# Power.net
KiCad netlist of a schematic drawn in Altium Designer
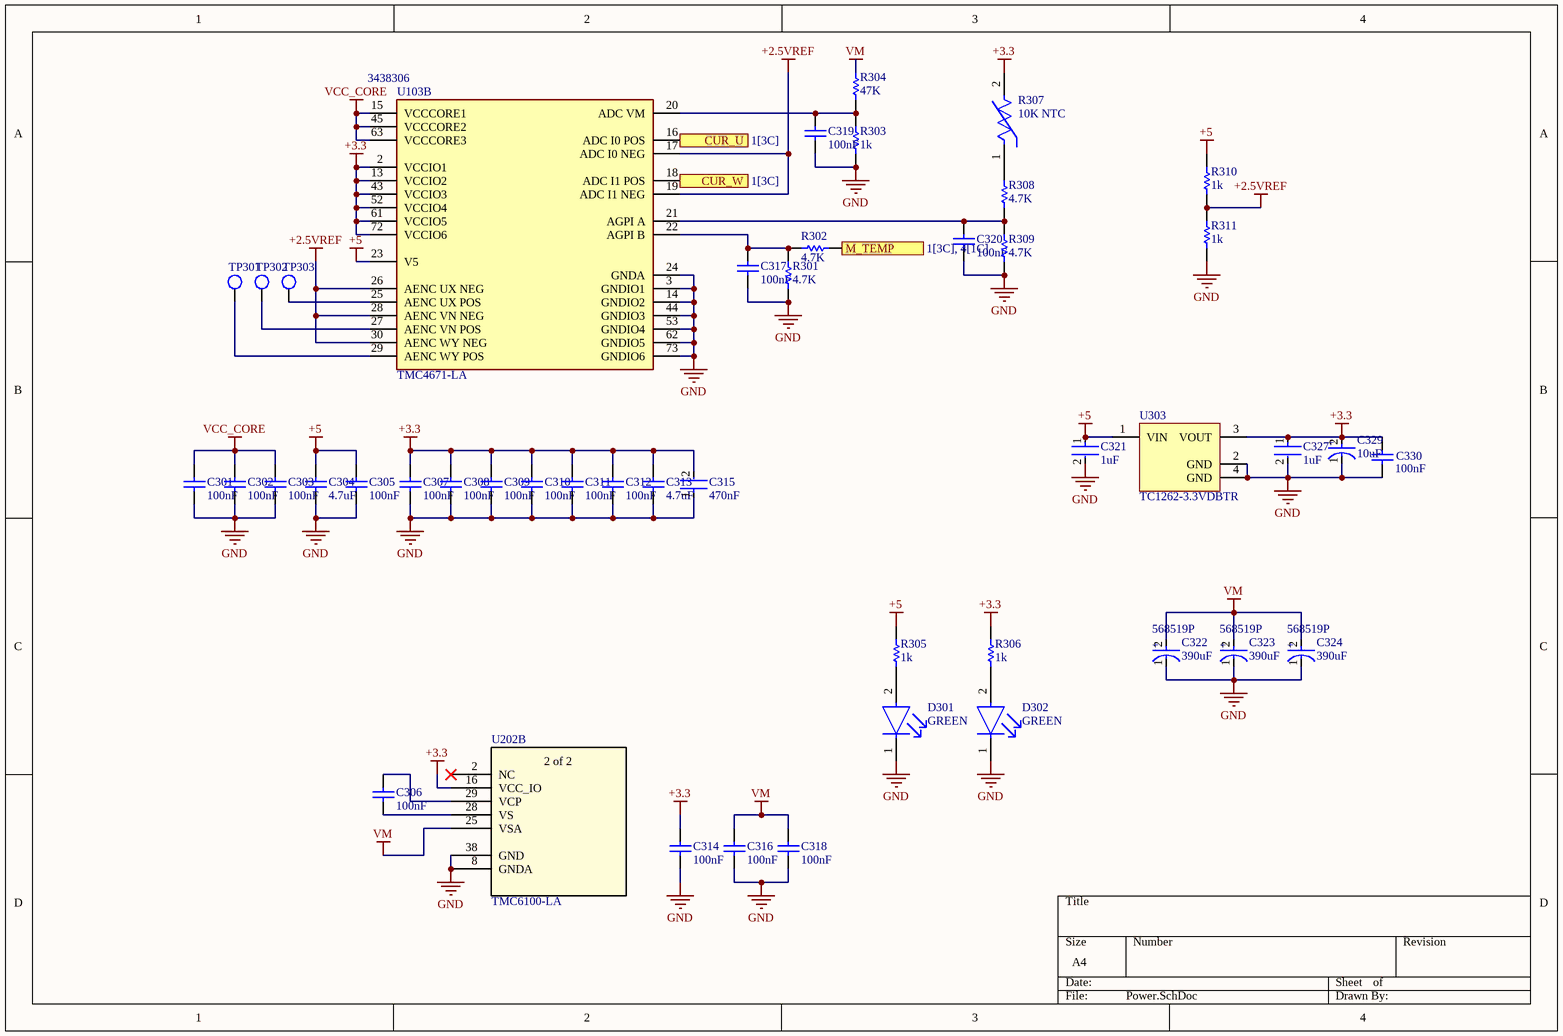
[diagram p0: Power.SchDoc]

(export (version "E")
  (design (tool "Eeschema 10.0.6"))
  (components
    (comp (ref "C301")
      (value "100nF")
      (footprint "CAPC1608X90X35NL10T15")
      (description "Chip Capacitor, 0.1 uF, +/- 10%, 50 V, -55 to 125 degC, 0603 (1608 Metric), RoHS, Tape and Reel")
      (fields (field (name "TOLERANCE") "10%") (field (name "VOLTAGE") "50V"))
      (libsource (lib "Altium Content Vault") (part "CAP-NP-2"))
    )
    (comp (ref "C302")
      (value "100nF")
      (footprint "CAPC1608X90X35NL10T15")
      (description "Chip Capacitor, 0.1 uF, +/- 10%, 50 V, -55 to 125 degC, 0603 (1608 Metric), RoHS, Tape and Reel")
      (fields (field (name "TOLERANCE") "10%") (field (name "VOLTAGE") "50V"))
      (libsource (lib "Altium Content Vault") (part "CAP-NP-2"))
    )
    (comp (ref "C303")
      (value "100nF")
      (footprint "CAPC1608X90X35NL10T15")
      (description "Chip Capacitor, 0.1 uF, +/- 10%, 50 V, -55 to 125 degC, 0603 (1608 Metric), RoHS, Tape and Reel")
      (fields (field (name "TOLERANCE") "10%") (field (name "VOLTAGE") "50V"))
      (libsource (lib "Altium Content Vault") (part "CAP-NP-2"))
    )
    (comp (ref "C304")
      (value "4.7uF")
      (footprint "CAPC2013X145X50ML20T25")
      (fields (field (name "PART NUMBER") "C0805C475K4RACTU") (field (name "MANUFACTURER") "Kemet"))
      (libsource (lib "Altium Content Vault") (part "CAP"))
    )
    (comp (ref "C305")
      (value "100nF")
      (footprint "CAPC1608X90X35NL10T15")
      (description "Chip Capacitor, 0.1 uF, +/- 10%, 50 V, -55 to 125 degC, 0603 (1608 Metric), RoHS, Tape and Reel")
      (fields (field (name "TOLERANCE") "10%") (field (name "VOLTAGE") "50V"))
      (libsource (lib "Altium Content Vault") (part "CAP-NP-2"))
    )
    (comp (ref "C306")
      (value "100nF")
      (footprint "CAPC2013X145X20ML20")
      (description "Chip Capacitor, 100 nF, +/- 10%, 100 V, -55 to 1255 degC, 0805 (2012 Metric), RoHS, Tape and Reel")
      (fields (field (name "MANUFACTURER") "TDK") (field (name "TOLERANCE") "±10%"))
      (libsource (lib "Altium Content Vault") (part "CAP-NP-2"))
    )
    (comp (ref "C307")
      (value "100nF")
      (footprint "CAPC1608X90X35NL10T15")
      (description "Chip Capacitor, 0.1 uF, +/- 10%, 50 V, -55 to 125 degC, 0603 (1608 Metric), RoHS, Tape and Reel")
      (fields (field (name "TOLERANCE") "10%") (field (name "VOLTAGE") "50V"))
      (libsource (lib "Altium Content Vault") (part "CAP-NP-2"))
    )
    (comp (ref "C308")
      (value "100nF")
      (footprint "CAPC1608X90X35NL10T15")
      (description "Chip Capacitor, 0.1 uF, +/- 10%, 50 V, -55 to 125 degC, 0603 (1608 Metric), RoHS, Tape and Reel")
      (fields (field (name "TOLERANCE") "10%") (field (name "VOLTAGE") "50V"))
      (libsource (lib "Altium Content Vault") (part "CAP-NP-2"))
    )
    (comp (ref "C309")
      (value "100nF")
      (footprint "CAPC1608X90X35NL10T15")
      (description "Chip Capacitor, 0.1 uF, +/- 10%, 50 V, -55 to 125 degC, 0603 (1608 Metric), RoHS, Tape and Reel")
      (fields (field (name "TOLERANCE") "10%") (field (name "VOLTAGE") "50V"))
      (libsource (lib "Altium Content Vault") (part "CAP-NP-2"))
    )
    (comp (ref "C310")
      (value "100nF")
      (footprint "CAPC1608X90X35NL10T15")
      (description "Chip Capacitor, 0.1 uF, +/- 10%, 50 V, -55 to 125 degC, 0603 (1608 Metric), RoHS, Tape and Reel")
      (fields (field (name "TOLERANCE") "10%") (field (name "VOLTAGE") "50V"))
      (libsource (lib "Altium Content Vault") (part "CAP-NP-2"))
    )
    (comp (ref "C311")
      (value "100nF")
      (footprint "CAPC1608X90X35NL10T15")
      (description "Chip Capacitor, 0.1 uF, +/- 10%, 50 V, -55 to 125 degC, 0603 (1608 Metric), RoHS, Tape and Reel")
      (fields (field (name "TOLERANCE") "10%") (field (name "VOLTAGE") "50V"))
      (libsource (lib "Altium Content Vault") (part "CAP-NP-2"))
    )
    (comp (ref "C312")
      (value "100nF")
      (footprint "CAPC1608X90X35NL10T15")
      (description "Chip Capacitor, 0.1 uF, +/- 10%, 50 V, -55 to 125 degC, 0603 (1608 Metric), RoHS, Tape and Reel")
      (fields (field (name "TOLERANCE") "10%") (field (name "VOLTAGE") "50V"))
      (libsource (lib "Altium Content Vault") (part "CAP-NP-2"))
    )
    (comp (ref "C313")
      (value "4.7uF")
      (footprint "CAPC2013X145X50ML20T25")
      (fields (field (name "PART NUMBER") "C0805C475K4RACTU") (field (name "MANUFACTURER") "Kemet"))
      (libsource (lib "Altium Content Vault") (part "CAP"))
    )
    (comp (ref "C314")
      (value "100nF")
      (footprint "CAPC1608X90X35NL10T15")
      (description "Chip Capacitor, 0.1 uF, +/- 10%, 50 V, -55 to 125 degC, 0603 (1608 Metric), RoHS, Tape and Reel")
      (fields (field (name "TOLERANCE") "10%") (field (name "VOLTAGE") "50V"))
      (libsource (lib "Altium Content Vault") (part "CAP-NP-2"))
    )
    (comp (ref "C315")
      (value "470nF")
      (footprint "FP-0603-L_1_6_0_1-W_0_8_0-IPC_B")
      (description "None")
      (fields (field (name "TOLERANCE") "10%") (field (name "VOLTAGE") "50V"))
      (libsource (lib "Altium Content Vault") (part "02cd4be3c70576c341d710602a673aa"))
    )
    (comp (ref "C316")
      (value "100nF")
      (footprint "CAPC2013X145X20ML20")
      (description "Chip Capacitor, 100 nF, +/- 10%, 100 V, -55 to 1255 degC, 0805 (2012 Metric), RoHS, Tape and Reel")
      (fields (field (name "MANUFACTURER") "TDK") (field (name "TOLERANCE") "±10%"))
      (libsource (lib "Altium Content Vault") (part "CAP-NP-2"))
    )
    (comp (ref "C317")
      (value "100nF")
      (footprint "CAPC1608X90X35NL10T15")
      (description "Chip Capacitor, 0.1 uF, +/- 10%, 50 V, -55 to 125 degC, 0603 (1608 Metric), RoHS, Tape and Reel")
      (fields (field (name "TOLERANCE") "10%") (field (name "VOLTAGE") "50V"))
      (libsource (lib "Altium Content Vault") (part "CAP-NP-2"))
    )
    (comp (ref "C318")
      (value "100nF")
      (footprint "CAPC2013X145X20ML20")
      (description "Chip Capacitor, 100 nF, +/- 10%, 100 V, -55 to 1255 degC, 0805 (2012 Metric), RoHS, Tape and Reel")
      (fields (field (name "MANUFACTURER") "TDK") (field (name "TOLERANCE") "±10%"))
      (libsource (lib "Altium Content Vault") (part "CAP-NP-2"))
    )
    (comp (ref "C319")
      (value "100nF")
      (footprint "CAPC1608X90X35NL10T15")
      (description "Chip Capacitor, 0.1 uF, +/- 10%, 50 V, -55 to 125 degC, 0603 (1608 Metric), RoHS, Tape and Reel")
      (fields (field (name "TOLERANCE") "10%") (field (name "VOLTAGE") "50V"))
      (libsource (lib "Altium Content Vault") (part "CAP-NP-2"))
    )
    (comp (ref "C320")
      (value "100nF")
      (footprint "CAPC1608X90X35NL10T15")
      (description "Chip Capacitor, 0.1 uF, +/- 10%, 50 V, -55 to 125 degC, 0603 (1608 Metric), RoHS, Tape and Reel")
      (fields (field (name "TOLERANCE") "10%") (field (name "VOLTAGE") "50V"))
      (libsource (lib "Altium Content Vault") (part "CAP-NP-2"))
    )
    (comp (ref "C321")
      (value "1uF")
      (footprint "FP-CL10-IPC_B")
      (description "Cap Ceramic 1uF 25V X5R ±10% Pad SMD 0603 +85°C T/R")
      (fields (field (name "VOLTAGE") "25V") (field (name "TOLERANCE") "10%"))
      (libsource (lib "Altium Content Vault") (part "b4654b650e69147ec39a6b967a45e02"))
    )
    (comp (ref "C322")
      (value "390uF")
      (footprint "FP-FC-G-MFG")
      (description "Cap Aluminum 390uF 35V 20% (10 X 10.2mm) SMD 0.08 Ohm 850mA 2000 hr 105°C Embossed T/R")
      (fields
        (field (name "TOLERANCE") "20%")
        (field (name "VOLTAGE") "35V")
        (field (name "SUPPLIER PART NUMBER 1") "568519P")
      )
      (libsource (lib "Altium Content Vault") (part "8eef7423fb450d55d321f8a63fae760"))
    )
    (comp (ref "C323")
      (value "390uF")
      (footprint "FP-FC-G-MFG")
      (description "Cap Aluminum 390uF 35V 20% (10 X 10.2mm) SMD 0.08 Ohm 850mA 2000 hr 105°C Embossed T/R")
      (fields
        (field (name "TOLERANCE") "20%")
        (field (name "VOLTAGE") "35V")
        (field (name "SUPPLIER PART NUMBER 1") "568519P")
      )
      (libsource (lib "Altium Content Vault") (part "8eef7423fb450d55d321f8a63fae760"))
    )
    (comp (ref "C324")
      (value "390uF")
      (footprint "FP-FC-G-MFG")
      (description "Cap Aluminum 390uF 35V 20% (10 X 10.2mm) SMD 0.08 Ohm 850mA 2000 hr 105°C Embossed T/R")
      (fields
        (field (name "TOLERANCE") "20%")
        (field (name "VOLTAGE") "35V")
        (field (name "SUPPLIER PART NUMBER 1") "568519P")
      )
      (libsource (lib "Altium Content Vault") (part "8eef7423fb450d55d321f8a63fae760"))
    )
    (comp (ref "C327")
      (value "1uF")
      (footprint "FP-CL10-IPC_B")
      (description "Cap Ceramic 1uF 25V X5R ±10% Pad SMD 0603 +85°C T/R")
      (fields (field (name "VOLTAGE") "25V") (field (name "TOLERANCE") "10%"))
      (libsource (lib "Altium Content Vault") (part "b4654b650e69147ec39a6b967a45e02"))
    )
    (comp (ref "C329")
      (value "10uF")
      (footprint "FP-TAJA-MFG")
      (description "10uF 10V  ±10% 3Ω 1206  SMD Tantalum Capacitor")
      (fields (field (name "TOLERANCE") "10%") (field (name "VOLTAGE") "10V"))
      (libsource (lib "Altium Content Vault") (part "203bc49f2ac43e59fd269a8c329ed05"))
    )
    (comp (ref "C330")
      (value "100nF")
      (footprint "CAPC1608X90X35NL10T15")
      (description "Chip Capacitor, 0.1 uF, +/- 10%, 50 V, -55 to 125 degC, 0603 (1608 Metric), RoHS, Tape and Reel")
      (fields (field (name "TOLERANCE") "10%") (field (name "VOLTAGE") "50V"))
      (libsource (lib "Altium Content Vault") (part "CAP-NP-2"))
    )
    (comp (ref "D301")
      (value "GREEN")
      (footprint "FP-LTST-C190GKT-MFG")
      (description "LED GREEN CLEAR CHIP SMD")
      (fields (field (name "VOLTAGE") "2V"))
      (libsource (lib "Altium Content Vault") (part "8706943c75ba83719d021d2fdc84c58"))
    )
    (comp (ref "D302")
      (value "GREEN")
      (footprint "FP-LTST-C190GKT-MFG")
      (description "LED GREEN CLEAR CHIP SMD")
      (fields (field (name "VOLTAGE") "2V"))
      (libsource (lib "Altium Content Vault") (part "8706943c75ba83719d021d2fdc84c58"))
    )
    (comp (ref "R301")
      (value "4.7K")
      (footprint "RESC1608X55X30NL15T15")
      (fields (field (name "TOLERANCE") "5%"))
      (libsource (lib "Altium Content Vault") (part "RES-2"))
    )
    (comp (ref "R302")
      (value "4.7K")
      (footprint "RESC1608X55X30NL15T15")
      (fields (field (name "TOLERANCE") "5%"))
      (libsource (lib "Altium Content Vault") (part "RES-2"))
    )
    (comp (ref "R303")
      (value "1k")
      (footprint "RESC1608X55X30ML15T15")
      (fields (field (name "PART NUMBER") "ERJ-3EKF1001V") (field (name "MANUFACTURER") "Panasonic"))
      (libsource (lib "Altium Content Vault") (part "RES"))
    )
    (comp (ref "R304")
      (value "47K")
      (footprint "RESC1608X55X30NL15T15")
      (description "Chip Resistor, 47 KOhm, +/- 1%, 0.1 W, -55 to 155 degC, 0603 (1608 Metric), RoHS, Tape and Reel")
      (libsource (lib "Altium Content Vault") (part "RES-2"))
    )
    (comp (ref "R305")
      (value "1k")
      (footprint "RESC1608X55X30ML15T15")
      (fields (field (name "PART NUMBER") "ERJ-3EKF1001V") (field (name "MANUFACTURER") "Panasonic"))
      (libsource (lib "Altium Content Vault") (part "RES"))
    )
    (comp (ref "R306")
      (value "1k")
      (footprint "RESC1608X55X30ML15T15")
      (fields (field (name "PART NUMBER") "ERJ-3EKF1001V") (field (name "MANUFACTURER") "Panasonic"))
      (libsource (lib "Altium Content Vault") (part "RES"))
    )
    (comp (ref "R307")
      (value "10K NTC")
      (footprint "FP-NCP18-0_15-IPC_A")
      (description "NTC Thermistor for Temperature Sensor, 0603, 10kΩ, 1%, 0.1mA, 5V")
      (fields (field (name "TOLERANCE") "1%"))
      (libsource (lib "Altium Content Vault") (part "3b148a6ebabc5fb4d708a66c052d352"))
    )
    (comp (ref "R308")
      (value "4.7K")
      (footprint "RESC1608X55X30NL15T15")
      (fields (field (name "TOLERANCE") "5%"))
      (libsource (lib "Altium Content Vault") (part "RES-2"))
    )
    (comp (ref "R309")
      (value "4.7K")
      (footprint "RESC1608X55X30NL15T15")
      (fields (field (name "TOLERANCE") "5%"))
      (libsource (lib "Altium Content Vault") (part "RES-2"))
    )
    (comp (ref "R310")
      (value "1k")
      (footprint "RESC1608X55X30ML15T15")
      (fields (field (name "PART NUMBER") "ERJ-3EKF1001V") (field (name "MANUFACTURER") "Panasonic"))
      (libsource (lib "Altium Content Vault") (part "RES"))
    )
    (comp (ref "R311")
      (value "1k")
      (footprint "RESC1608X55X30ML15T15")
      (fields (field (name "PART NUMBER") "ERJ-3EKF1001V") (field (name "MANUFACTURER") "Panasonic"))
      (libsource (lib "Altium Content Vault") (part "RES"))
    )
    (comp (ref "TP301")
      (value "TestPoint")
      (footprint "PCBComponent_1")
      (libsource (lib "Testpoint") (part "TestPoint"))
    )
    (comp (ref "TP302")
      (value "TestPoint")
      (footprint "PCBComponent_1")
      (libsource (lib "Testpoint") (part "TestPoint"))
    )
    (comp (ref "TP303")
      (value "TestPoint")
      (footprint "PCBComponent_1")
      (libsource (lib "Testpoint") (part "TestPoint"))
    )
    (comp (ref "U103")
      (value "TMC4671-LA")
      (footprint "FP-TMC4671-LA-IPC_A")
      (description "SERVO CONTROLLER IC, QFN76")
      (fields (field (name "SUPPLIER PART NUMBER 1") "3438306"))
      (libsource (lib "Altium Content Vault") (part "fddf9d8c5dbc63ee6fb3cd60f877672"))
    )
    (comp (ref "U202")
      (value "TMC6100-LA")
      (footprint "QFN37_7X7_TRI-M")
      (description "No Description Available")
      (libsource (lib "TMC6100-LA") (part "TMC6100-LA"))
    )
    (comp (ref "U303")
      (value "TC1262-3.3VDBTR")
      (footprint "SOT-223-DB3_N")
      (description "500mA Fixed Output CMOS LDO, 3-Pin SOT-223, Extended Temperature, Tape and Reel")
      (libsource (lib "Altium Content Vault") (part "PM-LINEREG-TC1262-IL4"))
    )
  )
  (nets
    (net (code "1") (name "+2.5VREF") (class "Default")
      (node (ref "R310") (pin "1") (pinfunction "1_1") (pintype "passive"))
      (node (ref "R311") (pin "2") (pinfunction "2_2") (pintype "passive"))
      (node (ref "U103") (pin "17") (pinfunction "ADC_I0_NEG_17") (pintype "passive"))
      (node (ref "U103") (pin "19") (pinfunction "ADC_I1_NEG_19") (pintype "passive"))
      (node (ref "U103") (pin "26") (pinfunction "AENC_UX_NEG_26") (pintype "passive"))
      (node (ref "U103") (pin "28") (pinfunction "AENC_VN_NEG_28") (pintype "passive"))
      (node (ref "U103") (pin "30") (pinfunction "AENC_WY_NEG_30") (pintype "passive"))
    )
    (net (code "2") (name "+3.3") (class "Default")
      (node (ref "C307") (pin "2") (pinfunction "2_2") (pintype "passive"))
      (node (ref "C308") (pin "2") (pinfunction "2_2") (pintype "passive"))
      (node (ref "C309") (pin "2") (pinfunction "2_2") (pintype "passive"))
      (node (ref "C310") (pin "2") (pinfunction "2_2") (pintype "passive"))
      (node (ref "C311") (pin "2") (pinfunction "2_2") (pintype "passive"))
      (node (ref "C312") (pin "2") (pinfunction "2_2") (pintype "passive"))
      (node (ref "C313") (pin "2") (pinfunction "2_2") (pintype "passive"))
      (node (ref "C314") (pin "2") (pinfunction "2_2") (pintype "passive"))
      (node (ref "C315") (pin "2") (pinfunction "2_2") (pintype "passive"))
      (node (ref "C327") (pin "1") (pinfunction "1_1") (pintype "passive"))
      (node (ref "C329") (pin "2") (pinfunction "A_2") (pintype "passive"))
      (node (ref "C330") (pin "2") (pinfunction "2_2") (pintype "passive"))
      (node (ref "R306") (pin "2") (pinfunction "2_2") (pintype "passive"))
      (node (ref "R307") (pin "2") (pinfunction "2_2") (pintype "passive"))
      (node (ref "U103") (pin "13") (pinfunction "VCCIO2_13") (pintype "power_in"))
      (node (ref "U103") (pin "2") (pinfunction "VCCIO1_2") (pintype "power_in"))
      (node (ref "U103") (pin "43") (pinfunction "VCCIO3_43") (pintype "power_in"))
      (node (ref "U103") (pin "52") (pinfunction "VCCIO4_52") (pintype "power_in"))
      (node (ref "U103") (pin "61") (pinfunction "VCCIO5_61") (pintype "power_in"))
      (node (ref "U103") (pin "72") (pinfunction "VCCIO6_72") (pintype "power_in"))
      (node (ref "U202") (pin "16") (pinfunction "VCC_IO_16") (pintype "power_in"))
      (node (ref "U303") (pin "3") (pinfunction "VOUT_3") (pintype "power_in"))
    )
    (net (code "3") (name "+5") (class "Default")
      (node (ref "C304") (pin "2") (pinfunction "2_2") (pintype "passive"))
      (node (ref "C305") (pin "2") (pinfunction "2_2") (pintype "passive"))
      (node (ref "C321") (pin "1") (pinfunction "1_1") (pintype "passive"))
      (node (ref "R305") (pin "2") (pinfunction "2_2") (pintype "passive"))
      (node (ref "R310") (pin "2") (pinfunction "2_2") (pintype "passive"))
      (node (ref "U103") (pin "23") (pinfunction "V5_23") (pintype "power_in"))
      (node (ref "U303") (pin "1") (pinfunction "VIN_1") (pintype "power_in"))
    )
    (net (code "4") (name "/CUR_U") (class "Default")
      (node (ref "U103") (pin "16") (pinfunction "ADC_I0_POS_16") (pintype "passive"))
    )
    (net (code "5") (name "/CUR_W") (class "Default")
      (node (ref "U103") (pin "18") (pinfunction "ADC_I1_POS_18") (pintype "passive"))
    )
    (net (code "6") (name "/M_TEMP") (class "Default")
      (node (ref "R302") (pin "2") (pinfunction "2_2") (pintype "passive"))
    )
    (net (code "7") (name "GND") (class "Default")
      (node (ref "C301") (pin "1") (pinfunction "1_1") (pintype "passive"))
      (node (ref "C302") (pin "1") (pinfunction "1_1") (pintype "passive"))
      (node (ref "C303") (pin "1") (pinfunction "1_1") (pintype "passive"))
      (node (ref "C304") (pin "1") (pinfunction "1_1") (pintype "passive"))
      (node (ref "C305") (pin "1") (pinfunction "1_1") (pintype "passive"))
      (node (ref "C307") (pin "1") (pinfunction "1_1") (pintype "passive"))
      (node (ref "C308") (pin "1") (pinfunction "1_1") (pintype "passive"))
      (node (ref "C309") (pin "1") (pinfunction "1_1") (pintype "passive"))
      (node (ref "C310") (pin "1") (pinfunction "1_1") (pintype "passive"))
      (node (ref "C311") (pin "1") (pinfunction "1_1") (pintype "passive"))
      (node (ref "C312") (pin "1") (pinfunction "1_1") (pintype "passive"))
      (node (ref "C313") (pin "1") (pinfunction "1_1") (pintype "passive"))
      (node (ref "C314") (pin "1") (pinfunction "1_1") (pintype "passive"))
      (node (ref "C315") (pin "1") (pinfunction "1_1") (pintype "passive"))
      (node (ref "C316") (pin "2") (pinfunction "2_2") (pintype "passive"))
      (node (ref "C317") (pin "1") (pinfunction "1_1") (pintype "passive"))
      (node (ref "C318") (pin "2") (pinfunction "2_2") (pintype "passive"))
      (node (ref "C319") (pin "1") (pinfunction "1_1") (pintype "passive"))
      (node (ref "C320") (pin "1") (pinfunction "1_1") (pintype "passive"))
      (node (ref "C321") (pin "2") (pinfunction "2_2") (pintype "passive"))
      (node (ref "C322") (pin "1") (pinfunction "C_1") (pintype "passive"))
      (node (ref "C323") (pin "1") (pinfunction "C_1") (pintype "passive"))
      (node (ref "C324") (pin "1") (pinfunction "C_1") (pintype "passive"))
      (node (ref "C327") (pin "2") (pinfunction "2_2") (pintype "passive"))
      (node (ref "C329") (pin "1") (pinfunction "C_1") (pintype "passive"))
      (node (ref "C330") (pin "1") (pinfunction "1_1") (pintype "passive"))
      (node (ref "D301") (pin "1") (pinfunction "C_1") (pintype "passive"))
      (node (ref "D302") (pin "1") (pinfunction "C_1") (pintype "passive"))
      (node (ref "R301") (pin "1") (pinfunction "1_1") (pintype "passive"))
      (node (ref "R303") (pin "1") (pinfunction "1_1") (pintype "passive"))
      (node (ref "R309") (pin "1") (pinfunction "1_1") (pintype "passive"))
      (node (ref "R311") (pin "1") (pinfunction "1_1") (pintype "passive"))
      (node (ref "U103") (pin "14") (pinfunction "GNDIO2_14") (pintype "power_in"))
      (node (ref "U103") (pin "24") (pinfunction "GNDA_24") (pintype "power_in"))
      (node (ref "U103") (pin "3") (pinfunction "GNDIO1_3") (pintype "power_in"))
      (node (ref "U103") (pin "44") (pinfunction "GNDIO3_44") (pintype "power_in"))
      (node (ref "U103") (pin "53") (pinfunction "GNDIO4_53") (pintype "power_in"))
      (node (ref "U103") (pin "62") (pinfunction "GNDIO5_62") (pintype "power_in"))
      (node (ref "U103") (pin "73") (pinfunction "GNDIO6_73") (pintype "power_in"))
      (node (ref "U202") (pin "38") (pinfunction "GND_38") (pintype "power_in"))
      (node (ref "U202") (pin "8") (pinfunction "GNDA_8") (pintype "power_in"))
      (node (ref "U303") (pin "2") (pinfunction "GND_2") (pintype "power_in"))
      (node (ref "U303") (pin "4") (pinfunction "GND_4") (pintype "power_in"))
    )
    (net (code "8") (name "Net-(D301-A)") (class "Default")
      (node (ref "D301") (pin "2") (pinfunction "A_2") (pintype "passive"))
      (node (ref "R305") (pin "1") (pinfunction "1_1") (pintype "passive"))
    )
    (net (code "9") (name "Net-(D302-A)") (class "Default")
      (node (ref "D302") (pin "2") (pinfunction "A_2") (pintype "passive"))
      (node (ref "R306") (pin "1") (pinfunction "1_1") (pintype "passive"))
    )
    (net (code "10") (name "Net-(R307-Pad1)") (class "Default")
      (node (ref "R307") (pin "1") (pinfunction "1_1") (pintype "passive"))
      (node (ref "R308") (pin "2") (pinfunction "2_2") (pintype "passive"))
    )
    (net (code "11") (name "Net-(U103B-ADC_VM)") (class "Default")
      (node (ref "C319") (pin "2") (pinfunction "2_2") (pintype "passive"))
      (node (ref "R303") (pin "2") (pinfunction "2_2") (pintype "passive"))
      (node (ref "R304") (pin "1") (pinfunction "1_1") (pintype "passive"))
      (node (ref "U103") (pin "20") (pinfunction "ADC_VM_20") (pintype "passive"))
    )
    (net (code "12") (name "Net-(U103B-AENC_UX_POS)") (class "Default")
      (node (ref "TP303") (pin "1") (pinfunction "1_1") (pintype "passive"))
      (node (ref "U103") (pin "25") (pinfunction "AENC_UX_POS_25") (pintype "passive"))
    )
    (net (code "13") (name "Net-(U103B-AENC_VN_POS)") (class "Default")
      (node (ref "TP302") (pin "1") (pinfunction "1_1") (pintype "passive"))
      (node (ref "U103") (pin "27") (pinfunction "AENC_VN_POS_27") (pintype "passive"))
    )
    (net (code "14") (name "Net-(U103B-AENC_WY_POS)") (class "Default")
      (node (ref "TP301") (pin "1") (pinfunction "1_1") (pintype "passive"))
      (node (ref "U103") (pin "29") (pinfunction "AENC_WY_POS_29") (pintype "passive"))
    )
    (net (code "15") (name "Net-(U103B-AGPI_A)") (class "Default")
      (node (ref "C320") (pin "2") (pinfunction "2_2") (pintype "passive"))
      (node (ref "R308") (pin "1") (pinfunction "1_1") (pintype "passive"))
      (node (ref "R309") (pin "2") (pinfunction "2_2") (pintype "passive"))
      (node (ref "U103") (pin "21") (pinfunction "AGPI_A_21") (pintype "passive"))
    )
    (net (code "16") (name "Net-(U103B-AGPI_B)") (class "Default")
      (node (ref "C317") (pin "2") (pinfunction "2_2") (pintype "passive"))
      (node (ref "R301") (pin "2") (pinfunction "2_2") (pintype "passive"))
      (node (ref "R302") (pin "1") (pinfunction "1_1") (pintype "passive"))
      (node (ref "U103") (pin "22") (pinfunction "AGPI_B_22") (pintype "passive"))
    )
    (net (code "17") (name "Net-(U202B-VCP)") (class "Default")
      (node (ref "C306") (pin "1") (pinfunction "1_1") (pintype "passive"))
      (node (ref "U202") (pin "29") (pinfunction "VCP_29") (pintype "power_in"))
    )
    (net (code "18") (name "Net-(U202B-VS)") (class "Default")
      (node (ref "C306") (pin "2") (pinfunction "2_2") (pintype "passive"))
      (node (ref "U202") (pin "28") (pinfunction "VS_28") (pintype "power_in"))
    )
    (net (code "19") (name "VCC_CORE") (class "Default")
      (node (ref "C301") (pin "2") (pinfunction "2_2") (pintype "passive"))
      (node (ref "C302") (pin "2") (pinfunction "2_2") (pintype "passive"))
      (node (ref "C303") (pin "2") (pinfunction "2_2") (pintype "passive"))
      (node (ref "U103") (pin "15") (pinfunction "VCCCORE1_15") (pintype "power_in"))
      (node (ref "U103") (pin "45") (pinfunction "VCCCORE2_45") (pintype "power_in"))
      (node (ref "U103") (pin "63") (pinfunction "VCCCORE3_63") (pintype "power_in"))
    )
    (net (code "20") (name "VM") (class "Default")
      (node (ref "C316") (pin "1") (pinfunction "1_1") (pintype "passive"))
      (node (ref "C318") (pin "1") (pinfunction "1_1") (pintype "passive"))
      (node (ref "C322") (pin "2") (pinfunction "A_2") (pintype "passive"))
      (node (ref "C323") (pin "2") (pinfunction "A_2") (pintype "passive"))
      (node (ref "C324") (pin "2") (pinfunction "A_2") (pintype "passive"))
      (node (ref "R304") (pin "2") (pinfunction "2_2") (pintype "passive"))
      (node (ref "U202") (pin "25") (pinfunction "VSA_25") (pintype "power_in"))
    )
    (net (code "21") (name "unconnected-(U202B-NC-Pad2)") (class "Default")
      (node (ref "U202") (pin "2") (pinfunction "NC_2") (pintype "passive+no_connect"))
    )
  )
)
